# BLE112Shield_v0_1.net
KiCad netlist of a schematic drawn in EAGLE
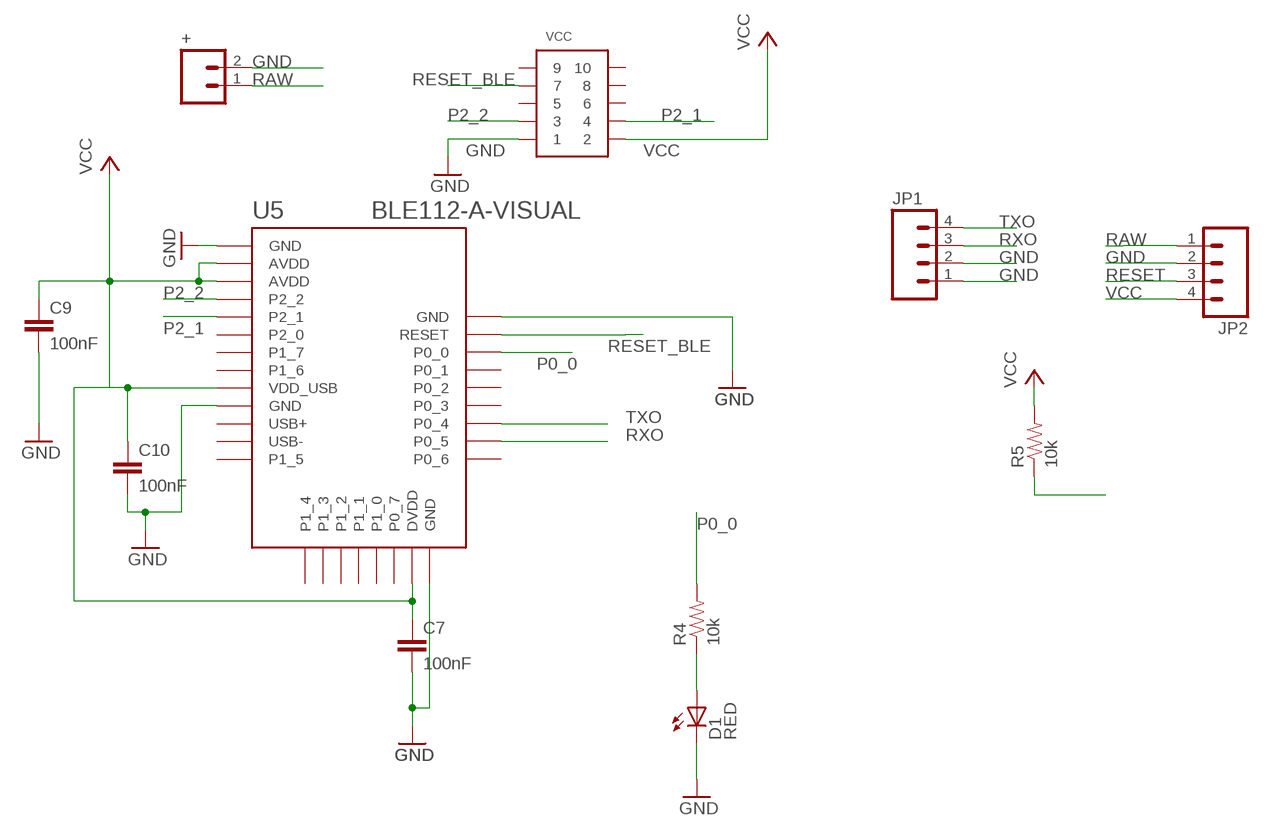
[diagram p0: schematic, sheet 1]

(export (version "E")
  (design (tool "Eeschema 10.0.6"))
  (components
    (comp (ref "+")
      (value "M021X02_NO_SILK")
      (footprint "eagle-import:1X02_NO_SILK")
      (libsource (lib "eagle-import") (part "M021X02_NO_SILK"))
    )
    (comp (ref "C7")
      (value "100nF")
      (footprint "eagle-import:0402-CAP")
      (libsource (lib "eagle-import") (part "CAP0402-CAP"))
    )
    (comp (ref "C9")
      (value "100nF")
      (footprint "eagle-import:0402-CAP")
      (libsource (lib "eagle-import") (part "CAP0402-CAP"))
    )
    (comp (ref "C10")
      (value "100nF")
      (footprint "eagle-import:0402-CAP")
      (libsource (lib "eagle-import") (part "CAP0402-CAP"))
    )
    (comp (ref "D1")
      (value "RED")
      (footprint "eagle-import:LED-0603")
      (libsource (lib "eagle-import") (part "LED-RED0603"))
    )
    (comp (ref "JP1")
      (value "M04PTH")
      (footprint "eagle-import:1X04")
      (libsource (lib "eagle-import") (part "M04PTH"))
    )
    (comp (ref "JP2")
      (value "M04PTH")
      (footprint "eagle-import:1X04")
      (libsource (lib "eagle-import") (part "M04PTH"))
    )
    (comp (ref "R4")
      (value "10k")
      (footprint "eagle-import:0402-RES")
      (libsource (lib "eagle-import") (part "RESISTOR0402-RES"))
    )
    (comp (ref "R5")
      (value "10k")
      (footprint "eagle-import:0402-RES")
      (libsource (lib "eagle-import") (part "RESISTOR0402-RES"))
    )
    (comp (ref "U5")
      (value "BLE112-A-VISUAL")
      (footprint "eagle-import:BLE112-A")
      (libsource (lib "eagle-import") (part "BLE112-A-VISUAL"))
    )
    (comp (ref "VCC")
      (value "CONN_5-2-FTSH-V")
      (footprint "eagle-import:FTSH-105-DV")
      (libsource (lib "eagle-import") (part "CONN_5-2-FTSH-V"))
    )
  )
  (nets
    (net (code "1") (name "/P0_0") (class "Default")
      (node (ref "R4") (pin "2") (pinfunction "2_2") (pintype "passive"))
      (node (ref "U5") (pin "P0_0") (pinfunction "P0_0_P0_0") (pintype "bidirectional"))
    )
    (net (code "2") (name "/P2_1") (class "Default")
      (node (ref "U5") (pin "P2_1") (pinfunction "P2_1_P2_1") (pintype "bidirectional"))
      (node (ref "VCC") (pin "4") (pinfunction "4_4") (pintype "bidirectional"))
    )
    (net (code "3") (name "/P2_2") (class "Default")
      (node (ref "U5") (pin "P2_2") (pinfunction "P2_2_P2_2") (pintype "bidirectional"))
      (node (ref "VCC") (pin "3") (pinfunction "3_3") (pintype "bidirectional"))
    )
    (net (code "4") (name "/RAW") (class "Default")
      (node (ref "+") (pin "1") (pinfunction "1_1") (pintype "passive"))
      (node (ref "JP2") (pin "1") (pinfunction "1_1") (pintype "passive"))
    )
    (net (code "5") (name "/RESET") (class "Default")
      (node (ref "JP2") (pin "3") (pinfunction "3_3") (pintype "passive"))
    )
    (net (code "6") (name "/RESET_BLE") (class "Default")
      (node (ref "R5") (pin "1") (pinfunction "1_1") (pintype "passive"))
      (node (ref "U5") (pin "RESET") (pinfunction "RESET_RESET") (pintype "input"))
      (node (ref "VCC") (pin "7") (pinfunction "7_7") (pintype "bidirectional"))
    )
    (net (code "7") (name "/RXO") (class "Default")
      (node (ref "JP1") (pin "3") (pinfunction "3_3") (pintype "passive"))
      (node (ref "U5") (pin "P0_5") (pinfunction "P0_5_P0_5") (pintype "bidirectional"))
    )
    (net (code "8") (name "/TXO") (class "Default")
      (node (ref "JP1") (pin "4") (pinfunction "4_4") (pintype "passive"))
      (node (ref "U5") (pin "P0_4") (pinfunction "P0_4_P0_4") (pintype "bidirectional"))
    )
    (net (code "9") (name "GND") (class "Default")
      (node (ref "+") (pin "2") (pinfunction "2_2") (pintype "passive"))
      (node (ref "C10") (pin "2") (pinfunction "2_2") (pintype "passive"))
      (node (ref "C7") (pin "2") (pinfunction "2_2") (pintype "passive"))
      (node (ref "C9") (pin "2") (pinfunction "2_2") (pintype "passive"))
      (node (ref "D1") (pin "C") (pinfunction "C_C") (pintype "passive"))
      (node (ref "JP1") (pin "1") (pinfunction "1_1") (pintype "passive"))
      (node (ref "JP1") (pin "2") (pinfunction "2_2") (pintype "passive"))
      (node (ref "JP2") (pin "2") (pinfunction "2_2") (pintype "passive"))
      (node (ref "U5") (pin "GND1") (pinfunction "GND_GND1") (pintype "power_in"))
      (node (ref "U5") (pin "GND2") (pinfunction "GND_GND2") (pintype "power_in"))
      (node (ref "U5") (pin "GND3") (pinfunction "GND_GND3") (pintype "power_in"))
      (node (ref "U5") (pin "GND4") (pinfunction "GND_GND4") (pintype "power_in"))
      (node (ref "VCC") (pin "1") (pinfunction "1_1") (pintype "bidirectional"))
    )
    (net (code "10") (name "Net-(D1-PadA)") (class "Default")
      (node (ref "D1") (pin "A") (pinfunction "A_A") (pintype "passive"))
      (node (ref "R4") (pin "1") (pinfunction "1_1") (pintype "passive"))
    )
    (net (code "11") (name "VCC") (class "Default")
      (node (ref "C10") (pin "1") (pinfunction "1_1") (pintype "passive"))
      (node (ref "C7") (pin "1") (pinfunction "1_1") (pintype "passive"))
      (node (ref "C9") (pin "1") (pinfunction "1_1") (pintype "passive"))
      (node (ref "JP2") (pin "4") (pinfunction "4_4") (pintype "passive"))
      (node (ref "R5") (pin "2") (pinfunction "2_2") (pintype "passive"))
      (node (ref "U5") (pin "AVDD1") (pinfunction "AVDD_AVDD1") (pintype "power_in"))
      (node (ref "U5") (pin "AVDD2") (pinfunction "AVDD_AVDD2") (pintype "power_in"))
      (node (ref "U5") (pin "DVDD") (pinfunction "DVDD_DVDD") (pintype "power_in"))
      (node (ref "U5") (pin "VDD_USB") (pinfunction "VDD_USB_VDD_USB") (pintype "power_in"))
      (node (ref "VCC") (pin "2") (pinfunction "2_2") (pintype "bidirectional"))
    )
    (net (code "12") (name "unconnected-(U5-PadP0_1)") (class "Default")
      (node (ref "U5") (pin "P0_1") (pinfunction "P0_1_P0_1") (pintype "bidirectional"))
    )
    (net (code "13") (name "unconnected-(U5-PadP0_2)") (class "Default")
      (node (ref "U5") (pin "P0_2") (pinfunction "P0_2_P0_2") (pintype "bidirectional"))
    )
    (net (code "14") (name "unconnected-(U5-PadP0_3)") (class "Default")
      (node (ref "U5") (pin "P0_3") (pinfunction "P0_3_P0_3") (pintype "bidirectional"))
    )
    (net (code "15") (name "unconnected-(U5-PadP0_6)") (class "Default")
      (node (ref "U5") (pin "P0_6") (pinfunction "P0_6_P0_6") (pintype "bidirectional"))
    )
    (net (code "16") (name "unconnected-(U5-PadP0_7)") (class "Default")
      (node (ref "U5") (pin "P0_7") (pinfunction "P0_7_P0_7") (pintype "bidirectional"))
    )
    (net (code "17") (name "unconnected-(U5-PadP1_0)") (class "Default")
      (node (ref "U5") (pin "P1_0") (pinfunction "P1_0_P1_0") (pintype "bidirectional"))
    )
    (net (code "18") (name "unconnected-(U5-PadP1_1)") (class "Default")
      (node (ref "U5") (pin "P1_1") (pinfunction "P1_1_P1_1") (pintype "bidirectional"))
    )
    (net (code "19") (name "unconnected-(U5-PadP1_2)") (class "Default")
      (node (ref "U5") (pin "P1_2") (pinfunction "P1_2_P1_2") (pintype "bidirectional"))
    )
    (net (code "20") (name "unconnected-(U5-PadP1_3)") (class "Default")
      (node (ref "U5") (pin "P1_3") (pinfunction "P1_3_P1_3") (pintype "bidirectional"))
    )
    (net (code "21") (name "unconnected-(U5-PadP1_4)") (class "Default")
      (node (ref "U5") (pin "P1_4") (pinfunction "P1_4_P1_4") (pintype "bidirectional"))
    )
    (net (code "22") (name "unconnected-(U5-PadP1_5)") (class "Default")
      (node (ref "U5") (pin "P1_5") (pinfunction "P1_5_P1_5") (pintype "bidirectional"))
    )
    (net (code "23") (name "unconnected-(U5-PadP1_6)") (class "Default")
      (node (ref "U5") (pin "P1_6") (pinfunction "P1_6_P1_6") (pintype "bidirectional"))
    )
    (net (code "24") (name "unconnected-(U5-PadP1_7)") (class "Default")
      (node (ref "U5") (pin "P1_7") (pinfunction "P1_7_P1_7") (pintype "bidirectional"))
    )
    (net (code "25") (name "unconnected-(U5-PadP2_0)") (class "Default")
      (node (ref "U5") (pin "P2_0") (pinfunction "P2_0_P2_0") (pintype "bidirectional"))
    )
    (net (code "26") (name "unconnected-(U5-PadUSB+)") (class "Default")
      (node (ref "U5") (pin "USB+") (pinfunction "USB+_USB+") (pintype "bidirectional"))
    )
    (net (code "27") (name "unconnected-(U5-PadUSB-)") (class "Default")
      (node (ref "U5") (pin "USB-") (pinfunction "USB-_USB-") (pintype "bidirectional"))
    )
    (net (code "28") (name "unconnected-(VCC-Pad5)") (class "Default")
      (node (ref "VCC") (pin "5") (pinfunction "5_5") (pintype "bidirectional"))
    )
    (net (code "29") (name "unconnected-(VCC-Pad6)") (class "Default")
      (node (ref "VCC") (pin "6") (pinfunction "6_6") (pintype "bidirectional"))
    )
    (net (code "30") (name "unconnected-(VCC-Pad8)") (class "Default")
      (node (ref "VCC") (pin "8") (pinfunction "8_8") (pintype "bidirectional"))
    )
    (net (code "31") (name "unconnected-(VCC-Pad9)") (class "Default")
      (node (ref "VCC") (pin "9") (pinfunction "9_9") (pintype "bidirectional"))
    )
    (net (code "32") (name "unconnected-(VCC-Pad10)") (class "Default")
      (node (ref "VCC") (pin "10") (pinfunction "10_10") (pintype "bidirectional"))
    )
  )
)
